# AVC-LAN-2.net
KiCad netlist of a schematic drawn in EAGLE
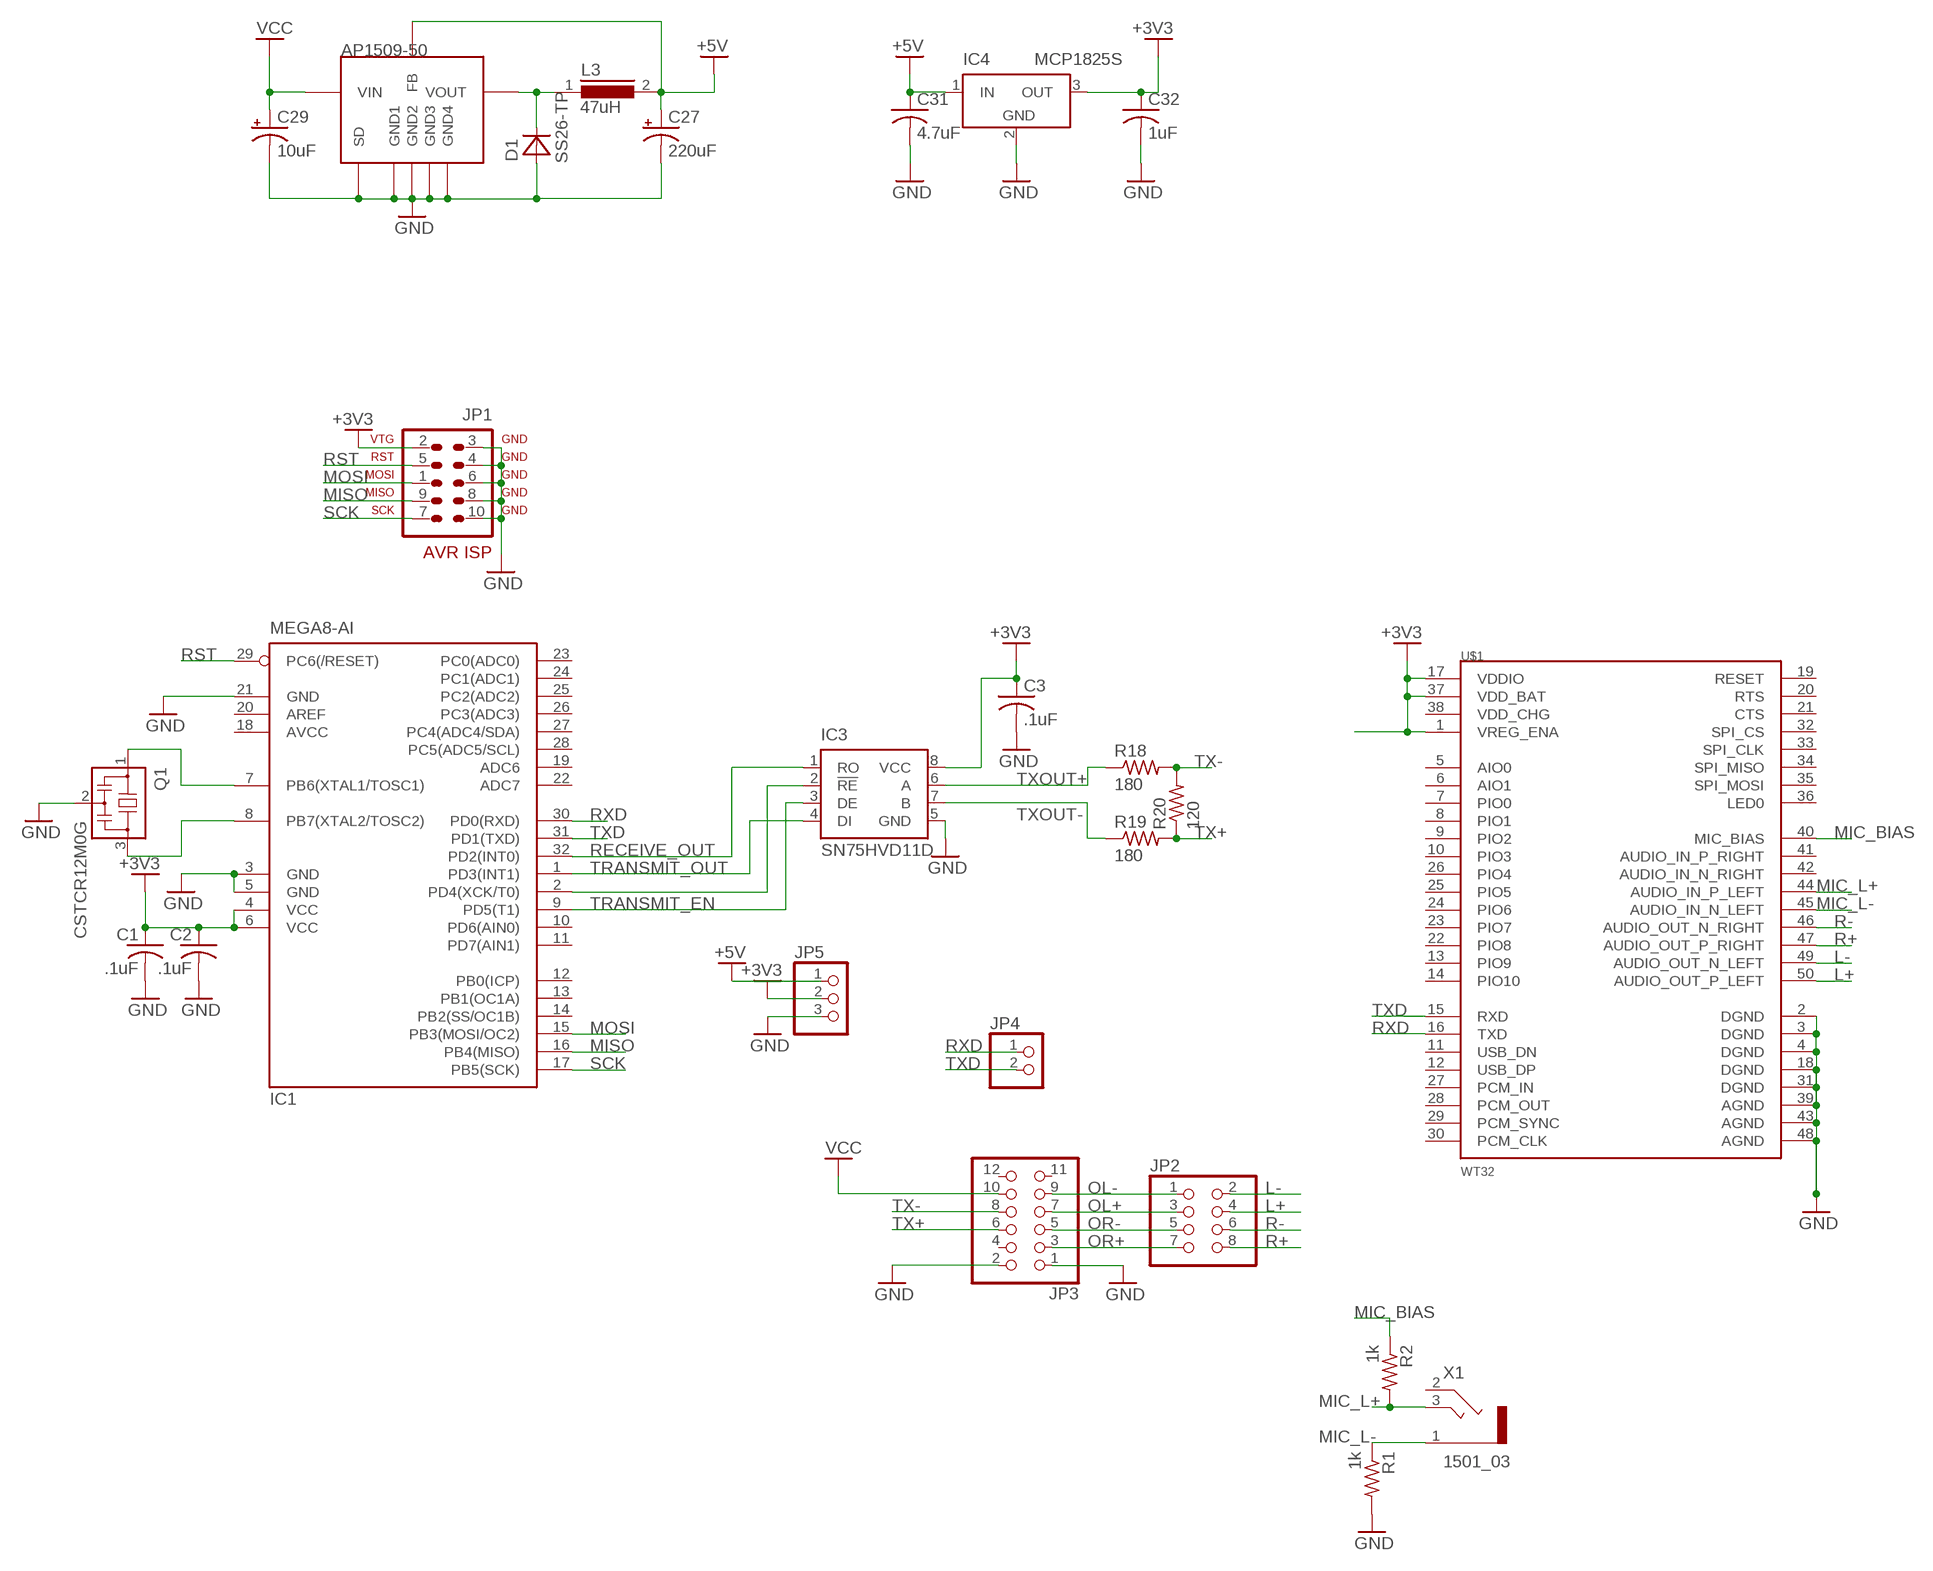
[diagram p0: schematic, sheet 1]

(export (version "E")
  (design (tool "Eeschema 10.0.6"))
  (components
    (comp (ref "C1")
      (value ".1uF")
      (footprint "eagle-import:C0603")
      (libsource (lib "eagle-import") (part "C-USC0603"))
    )
    (comp (ref "C2")
      (value ".1uF")
      (footprint "eagle-import:C0603")
      (libsource (lib "eagle-import") (part "C-USC0603"))
    )
    (comp (ref "C3")
      (value ".1uF")
      (footprint "eagle-import:C0603")
      (libsource (lib "eagle-import") (part "C-USC0603"))
    )
    (comp (ref "C27")
      (value "220uF")
      (footprint "eagle-import:D_7343-31W")
      (libsource (lib "eagle-import") (part "CPOL-USD/7343-31W"))
    )
    (comp (ref "C29")
      (value "10uF")
      (footprint "eagle-import:C_6032-28R")
      (libsource (lib "eagle-import") (part "CPOL-USC/6032-28R"))
    )
    (comp (ref "C31")
      (value "4.7uF")
      (footprint "eagle-import:C0603")
      (libsource (lib "eagle-import") (part "C-USC0603"))
    )
    (comp (ref "C32")
      (value "1uF")
      (footprint "eagle-import:C0603")
      (libsource (lib "eagle-import") (part "C-USC0603"))
    )
    (comp (ref "D1")
      (value "SS26-TP")
      (footprint "eagle-import:SMA")
      (libsource (lib "eagle-import") (part "MBRA340T3"))
    )
    (comp (ref "IC1")
      (value "MEGA8-AI")
      (footprint "eagle-import:TQFP32-08")
      (fields (field (name "MPN") "ATMEGA8-16AU"))
      (libsource (lib "eagle-import") (part "MEGA8-AI"))
    )
    (comp (ref "IC3")
      (value "SN75HVD11D")
      (footprint "eagle-import:SOIC8")
      (libsource (lib "eagle-import") (part "LTC485S"))
    )
    (comp (ref "IC4")
      (value "MCP1825S")
      (footprint "eagle-import:SOT223")
      (fields (field (name "MPN") "LT1963EST-3.3"))
      (libsource (lib "eagle-import") (part "LT1963EST-3.3"))
    )
    (comp (ref "JP1")
      (value "AVR-ISP-10R")
      (footprint "eagle-import:AVR-ISP-10R")
      (libsource (lib "eagle-import") (part "AVR-ISP-10R"))
    )
    (comp (ref "JP2")
      (value "PINHD-2X4")
      (footprint "eagle-import:2X04")
      (libsource (lib "eagle-import") (part "PINHD-2X4"))
    )
    (comp (ref "JP3")
      (value "PINHD-2X6/90")
      (footprint "eagle-import:2X06_90")
      (libsource (lib "eagle-import") (part "PINHD-2X6/90"))
    )
    (comp (ref "JP4")
      (value "PINHD-1X2")
      (footprint "eagle-import:1X02")
      (libsource (lib "eagle-import") (part "PINHD-1X2"))
    )
    (comp (ref "JP5")
      (value "PINHD-1X3")
      (footprint "eagle-import:1X03")
      (libsource (lib "eagle-import") (part "PINHD-1X3"))
    )
    (comp (ref "L3")
      (value "47uH")
      (footprint "eagle-import:DR125")
      (libsource (lib "eagle-import") (part "DR125"))
    )
    (comp (ref "Q1")
      (value "CSTCR12M0G")
      (footprint "eagle-import:CSTER12M")
      (fields (field (name "MPN") "CSTCC12M0") (field (name "MPN_1") "CSTCC12M0"))
      (libsource (lib "eagle-import") (part "CSTCR6M00G53Z"))
    )
    (comp (ref "R1")
      (value "1k")
      (footprint "eagle-import:R0603")
      (libsource (lib "eagle-import") (part "R-US_R0603"))
    )
    (comp (ref "R2")
      (value "1k")
      (footprint "eagle-import:R0603")
      (libsource (lib "eagle-import") (part "R-US_R0603"))
    )
    (comp (ref "R18")
      (value "180")
      (footprint "eagle-import:R0603")
      (libsource (lib "eagle-import") (part "R-US_R0603"))
    )
    (comp (ref "R19")
      (value "180")
      (footprint "eagle-import:R0603")
      (libsource (lib "eagle-import") (part "R-US_R0603"))
    )
    (comp (ref "R20")
      (value "120")
      (footprint "eagle-import:R0603")
      (libsource (lib "eagle-import") (part "R-US_R0603"))
    )
    (comp (ref "U$1")
      (value "WT32")
      (footprint "eagle-import:WT32")
      (libsource (lib "eagle-import") (part "WT32"))
    )
    (comp (ref "U$5")
      (value "AP1509-50")
      (footprint "eagle-import:SOP-8L")
      (libsource (lib "eagle-import") (part "AP1509-50"))
    )
    (comp (ref "X1")
      (value "1501_03")
      (footprint "eagle-import:1501_03")
      (libsource (lib "eagle-import") (part "1501_03"))
    )
  )
  (nets
    (net (code "1") (name "+3V3") (class "Default")
      (node (ref "C1") (pin "1") (pinfunction "1_1") (pintype "passive"))
      (node (ref "C2") (pin "1") (pinfunction "1_1") (pintype "passive"))
      (node (ref "C3") (pin "1") (pinfunction "1_1") (pintype "passive"))
      (node (ref "C32") (pin "1") (pinfunction "1_1") (pintype "passive"))
      (node (ref "IC1") (pin "4") (pinfunction "VCC_4") (pintype "power_in"))
      (node (ref "IC1") (pin "6") (pinfunction "VCC_6") (pintype "power_in"))
      (node (ref "IC3") (pin "8") (pinfunction "VCC_8") (pintype "input"))
      (node (ref "IC4") (pin "3") (pinfunction "OUT_3") (pintype "output"))
      (node (ref "JP1") (pin "2") (pinfunction "2_2") (pintype "passive"))
      (node (ref "JP5") (pin "2") (pinfunction "2_2") (pintype "passive"))
      (node (ref "U$1") (pin "1") (pinfunction "VREG_ENA_1") (pintype "bidirectional"))
      (node (ref "U$1") (pin "17") (pinfunction "VDDIO_17") (pintype "bidirectional"))
      (node (ref "U$1") (pin "37") (pinfunction "VDD_BAT_37") (pintype "bidirectional"))
    )
    (net (code "2") (name "+5V") (class "Default")
      (node (ref "C27") (pin "+") (pinfunction "+_+") (pintype "passive"))
      (node (ref "C31") (pin "1") (pinfunction "1_1") (pintype "passive"))
      (node (ref "IC4") (pin "1") (pinfunction "IN_1") (pintype "input"))
      (node (ref "JP5") (pin "1") (pinfunction "1_1") (pintype "passive"))
      (node (ref "L3") (pin "2") (pinfunction "2_2") (pintype "passive"))
      (node (ref "U$5") (pin "P$3") (pinfunction "FB_P$3") (pintype "bidirectional"))
    )
    (net (code "3") (name "/AVCC") (class "Default")
      (node (ref "IC1") (pin "18") (pinfunction "AVCC_18") (pintype "power_in"))
    )
    (net (code "4") (name "/L+") (class "Default")
      (node (ref "JP2") (pin "4") (pinfunction "4_4") (pintype "passive"))
      (node (ref "U$1") (pin "50") (pinfunction "AUDIO_OUT_P_LEFT_50") (pintype "bidirectional"))
    )
    (net (code "5") (name "/L-") (class "Default")
      (node (ref "JP2") (pin "2") (pinfunction "2_2") (pintype "passive"))
      (node (ref "U$1") (pin "49") (pinfunction "AUDIO_OUT_N_LEFT_49") (pintype "bidirectional"))
    )
    (net (code "6") (name "/MIC_BIAS") (class "Default")
      (node (ref "R2") (pin "1") (pinfunction "1_1") (pintype "passive"))
      (node (ref "U$1") (pin "40") (pinfunction "MIC_BIAS_40") (pintype "bidirectional"))
    )
    (net (code "7") (name "/MIC_L+") (class "Default")
      (node (ref "R2") (pin "2") (pinfunction "2_2") (pintype "passive"))
      (node (ref "U$1") (pin "44") (pinfunction "AUDIO_IN_P_LEFT_44") (pintype "bidirectional"))
      (node (ref "X1") (pin "3") (pinfunction "3_3") (pintype "passive"))
    )
    (net (code "8") (name "/MIC_L-") (class "Default")
      (node (ref "R1") (pin "1") (pinfunction "1_1") (pintype "passive"))
      (node (ref "U$1") (pin "45") (pinfunction "AUDIO_IN_N_LEFT_45") (pintype "bidirectional"))
      (node (ref "X1") (pin "1") (pinfunction "1_1") (pintype "passive"))
    )
    (net (code "9") (name "/MISO") (class "Default")
      (node (ref "IC1") (pin "16") (pinfunction "PB4(MISO)_16") (pintype "bidirectional"))
      (node (ref "JP1") (pin "9") (pinfunction "9_9") (pintype "passive"))
    )
    (net (code "10") (name "/MOSI") (class "Default")
      (node (ref "IC1") (pin "15") (pinfunction "PB3(MOSI/OC2)_15") (pintype "bidirectional"))
      (node (ref "JP1") (pin "1") (pinfunction "1_1") (pintype "passive"))
    )
    (net (code "11") (name "/OL+") (class "Default")
      (node (ref "JP2") (pin "3") (pinfunction "3_3") (pintype "passive"))
      (node (ref "JP3") (pin "7") (pinfunction "7_7") (pintype "passive"))
    )
    (net (code "12") (name "/OL-") (class "Default")
      (node (ref "JP2") (pin "1") (pinfunction "1_1") (pintype "passive"))
      (node (ref "JP3") (pin "9") (pinfunction "9_9") (pintype "passive"))
    )
    (net (code "13") (name "/OR+") (class "Default")
      (node (ref "JP2") (pin "7") (pinfunction "7_7") (pintype "passive"))
      (node (ref "JP3") (pin "3") (pinfunction "3_3") (pintype "passive"))
    )
    (net (code "14") (name "/OR-") (class "Default")
      (node (ref "JP2") (pin "5") (pinfunction "5_5") (pintype "passive"))
      (node (ref "JP3") (pin "5") (pinfunction "5_5") (pintype "passive"))
    )
    (net (code "15") (name "/R+") (class "Default")
      (node (ref "JP2") (pin "8") (pinfunction "8_8") (pintype "passive"))
      (node (ref "U$1") (pin "47") (pinfunction "AUDIO_OUT_P_RIGHT_47") (pintype "bidirectional"))
    )
    (net (code "16") (name "/R-") (class "Default")
      (node (ref "JP2") (pin "6") (pinfunction "6_6") (pintype "passive"))
      (node (ref "U$1") (pin "46") (pinfunction "AUDIO_OUT_N_RIGHT_46") (pintype "bidirectional"))
    )
    (net (code "17") (name "/RECEIVE_OUT") (class "Default")
      (node (ref "IC1") (pin "32") (pinfunction "PD2(INT0)_32") (pintype "bidirectional"))
      (node (ref "IC3") (pin "1") (pinfunction "RO_1") (pintype "output"))
    )
    (net (code "18") (name "/RST") (class "Default")
      (node (ref "IC1") (pin "29") (pinfunction "PC6(/RESET)_29") (pintype "bidirectional"))
      (node (ref "JP1") (pin "5") (pinfunction "5_5") (pintype "passive"))
    )
    (net (code "19") (name "/RXD") (class "Default")
      (node (ref "IC1") (pin "30") (pinfunction "PD0(RXD)_30") (pintype "bidirectional"))
      (node (ref "JP4") (pin "1") (pinfunction "1_1") (pintype "passive"))
      (node (ref "U$1") (pin "16") (pinfunction "TXD_16") (pintype "bidirectional"))
    )
    (net (code "20") (name "/SCK") (class "Default")
      (node (ref "IC1") (pin "17") (pinfunction "PB5(SCK)_17") (pintype "bidirectional"))
      (node (ref "JP1") (pin "7") (pinfunction "7_7") (pintype "passive"))
    )
    (net (code "21") (name "/TRANSMIT_EN") (class "Default")
      (node (ref "IC1") (pin "9") (pinfunction "PD5(T1)_9") (pintype "bidirectional"))
      (node (ref "IC3") (pin "3") (pinfunction "DE_3") (pintype "input"))
    )
    (net (code "22") (name "/TRANSMIT_OUT") (class "Default")
      (node (ref "IC1") (pin "1") (pinfunction "PD3(INT1)_1") (pintype "bidirectional"))
      (node (ref "IC3") (pin "4") (pinfunction "DI_4") (pintype "input"))
    )
    (net (code "23") (name "/TX+") (class "Default")
      (node (ref "JP3") (pin "6") (pinfunction "6_6") (pintype "passive"))
      (node (ref "R19") (pin "2") (pinfunction "2_2") (pintype "passive"))
      (node (ref "R20") (pin "1") (pinfunction "1_1") (pintype "passive"))
    )
    (net (code "24") (name "/TX-") (class "Default")
      (node (ref "JP3") (pin "8") (pinfunction "8_8") (pintype "passive"))
      (node (ref "R18") (pin "2") (pinfunction "2_2") (pintype "passive"))
      (node (ref "R20") (pin "2") (pinfunction "2_2") (pintype "passive"))
    )
    (net (code "25") (name "/TXD") (class "Default")
      (node (ref "IC1") (pin "31") (pinfunction "PD1(TXD)_31") (pintype "bidirectional"))
      (node (ref "JP4") (pin "2") (pinfunction "2_2") (pintype "passive"))
      (node (ref "U$1") (pin "15") (pinfunction "RXD_15") (pintype "bidirectional"))
    )
    (net (code "26") (name "/TXOUT+") (class "Default")
      (node (ref "IC3") (pin "6") (pinfunction "A_6") (pintype "bidirectional"))
      (node (ref "R18") (pin "1") (pinfunction "1_1") (pintype "passive"))
    )
    (net (code "27") (name "/TXOUT-") (class "Default")
      (node (ref "IC3") (pin "7") (pinfunction "B_7") (pintype "bidirectional"))
      (node (ref "R19") (pin "1") (pinfunction "1_1") (pintype "passive"))
    )
    (net (code "28") (name "GND") (class "Default")
      (node (ref "C1") (pin "2") (pinfunction "2_2") (pintype "passive"))
      (node (ref "C2") (pin "2") (pinfunction "2_2") (pintype "passive"))
      (node (ref "C27") (pin "-") (pinfunction "-_-") (pintype "passive"))
      (node (ref "C29") (pin "-") (pinfunction "-_-") (pintype "passive"))
      (node (ref "C3") (pin "2") (pinfunction "2_2") (pintype "passive"))
      (node (ref "C31") (pin "2") (pinfunction "2_2") (pintype "passive"))
      (node (ref "C32") (pin "2") (pinfunction "2_2") (pintype "passive"))
      (node (ref "D1") (pin "A") (pinfunction "A_A") (pintype "passive"))
      (node (ref "IC1") (pin "21") (pinfunction "GND_21") (pintype "power_in"))
      (node (ref "IC1") (pin "3") (pinfunction "GND_3") (pintype "power_in"))
      (node (ref "IC1") (pin "5") (pinfunction "GND_5") (pintype "power_in"))
      (node (ref "IC3") (pin "5") (pinfunction "GND_5") (pintype "input"))
      (node (ref "IC4") (pin "2") (pinfunction "GND_2") (pintype "power_in"))
      (node (ref "JP1") (pin "10") (pinfunction "10_10") (pintype "passive"))
      (node (ref "JP1") (pin "3") (pinfunction "3_3") (pintype "passive"))
      (node (ref "JP1") (pin "4") (pinfunction "4_4") (pintype "passive"))
      (node (ref "JP1") (pin "6") (pinfunction "6_6") (pintype "passive"))
      (node (ref "JP1") (pin "8") (pinfunction "8_8") (pintype "passive"))
      (node (ref "JP3") (pin "1") (pinfunction "1_1") (pintype "passive"))
      (node (ref "JP3") (pin "2") (pinfunction "2_2") (pintype "passive"))
      (node (ref "JP5") (pin "3") (pinfunction "3_3") (pintype "passive"))
      (node (ref "Q1") (pin "2") (pinfunction "2_2") (pintype "passive"))
      (node (ref "R1") (pin "2") (pinfunction "2_2") (pintype "passive"))
      (node (ref "U$1") (pin "18") (pinfunction "DGND_18") (pintype "bidirectional"))
      (node (ref "U$1") (pin "2") (pinfunction "DGND_2") (pintype "bidirectional"))
      (node (ref "U$1") (pin "3") (pinfunction "DGND_3") (pintype "bidirectional"))
      (node (ref "U$1") (pin "31") (pinfunction "DGND_31") (pintype "bidirectional"))
      (node (ref "U$1") (pin "39") (pinfunction "AGND_39") (pintype "bidirectional"))
      (node (ref "U$1") (pin "4") (pinfunction "DGND_4") (pintype "bidirectional"))
      (node (ref "U$1") (pin "43") (pinfunction "AGND_43") (pintype "bidirectional"))
      (node (ref "U$1") (pin "48") (pinfunction "AGND_48") (pintype "bidirectional"))
      (node (ref "U$5") (pin "P$4") (pinfunction "SD_P$4") (pintype "bidirectional"))
      (node (ref "U$5") (pin "P$5") (pinfunction "GND1_P$5") (pintype "bidirectional"))
      (node (ref "U$5") (pin "P$6") (pinfunction "GND2_P$6") (pintype "bidirectional"))
      (node (ref "U$5") (pin "P$7") (pinfunction "GND3_P$7") (pintype "bidirectional"))
      (node (ref "U$5") (pin "P$8") (pinfunction "GND4_P$8") (pintype "bidirectional"))
    )
    (net (code "29") (name "Net-(IC1-PB6(XTAL1{slash}TOSC1))") (class "Default")
      (node (ref "IC1") (pin "7") (pinfunction "PB6(XTAL1/TOSC1)_7") (pintype "bidirectional"))
      (node (ref "Q1") (pin "1") (pinfunction "1_1") (pintype "passive"))
    )
    (net (code "30") (name "Net-(IC1-PB7(XTAL2{slash}TOSC2))") (class "Default")
      (node (ref "IC1") (pin "8") (pinfunction "PB7(XTAL2/TOSC2)_8") (pintype "bidirectional"))
      (node (ref "Q1") (pin "3") (pinfunction "3_3") (pintype "passive"))
    )
    (net (code "31") (name "Net-(IC1-PD4(XCK{slash}T0))") (class "Default")
      (node (ref "IC1") (pin "2") (pinfunction "PD4(XCK/T0)_2") (pintype "bidirectional"))
      (node (ref "IC3") (pin "2") (pinfunction "~{RE}_2") (pintype "input"))
    )
    (net (code "32") (name "Net-(U$5-VOUT)") (class "Default")
      (node (ref "D1") (pin "C") (pinfunction "C_C") (pintype "passive"))
      (node (ref "L3") (pin "1") (pinfunction "1_1") (pintype "passive"))
      (node (ref "U$5") (pin "P$2") (pinfunction "VOUT_P$2") (pintype "power_in"))
    )
    (net (code "33") (name "VCC") (class "Default")
      (node (ref "C29") (pin "+") (pinfunction "+_+") (pintype "passive"))
      (node (ref "JP3") (pin "10") (pinfunction "10_10") (pintype "passive"))
      (node (ref "U$5") (pin "P$1") (pinfunction "VIN_P$1") (pintype "power_in"))
    )
    (net (code "34") (name "unconnected-(IC1-ADC6-Pad19)") (class "Default")
      (node (ref "IC1") (pin "19") (pinfunction "ADC6_19") (pintype "bidirectional"))
    )
    (net (code "35") (name "unconnected-(IC1-ADC7-Pad22)") (class "Default")
      (node (ref "IC1") (pin "22") (pinfunction "ADC7_22") (pintype "bidirectional"))
    )
    (net (code "36") (name "unconnected-(IC1-AREF-Pad20)") (class "Default")
      (node (ref "IC1") (pin "20") (pinfunction "AREF_20") (pintype "passive"))
    )
    (net (code "37") (name "unconnected-(IC1-PB0(ICP)-Pad12)") (class "Default")
      (node (ref "IC1") (pin "12") (pinfunction "PB0(ICP)_12") (pintype "bidirectional"))
    )
    (net (code "38") (name "unconnected-(IC1-PB1(OC1A)-Pad13)") (class "Default")
      (node (ref "IC1") (pin "13") (pinfunction "PB1(OC1A)_13") (pintype "bidirectional"))
    )
    (net (code "39") (name "unconnected-(IC1-PB2(SS{slash}OC1B)-Pad14)") (class "Default")
      (node (ref "IC1") (pin "14") (pinfunction "PB2(SS/OC1B)_14") (pintype "bidirectional"))
    )
    (net (code "40") (name "unconnected-(IC1-PC0(ADC0)-Pad23)") (class "Default")
      (node (ref "IC1") (pin "23") (pinfunction "PC0(ADC0)_23") (pintype "bidirectional"))
    )
    (net (code "41") (name "unconnected-(IC1-PC1(ADC1)-Pad24)") (class "Default")
      (node (ref "IC1") (pin "24") (pinfunction "PC1(ADC1)_24") (pintype "bidirectional"))
    )
    (net (code "42") (name "unconnected-(IC1-PC2(ADC2)-Pad25)") (class "Default")
      (node (ref "IC1") (pin "25") (pinfunction "PC2(ADC2)_25") (pintype "bidirectional"))
    )
    (net (code "43") (name "unconnected-(IC1-PC3(ADC3)-Pad26)") (class "Default")
      (node (ref "IC1") (pin "26") (pinfunction "PC3(ADC3)_26") (pintype "bidirectional"))
    )
    (net (code "44") (name "unconnected-(IC1-PC4(ADC4{slash}SDA)-Pad27)") (class "Default")
      (node (ref "IC1") (pin "27") (pinfunction "PC4(ADC4/SDA)_27") (pintype "bidirectional"))
    )
    (net (code "45") (name "unconnected-(IC1-PC5(ADC5{slash}SCL)-Pad28)") (class "Default")
      (node (ref "IC1") (pin "28") (pinfunction "PC5(ADC5/SCL)_28") (pintype "bidirectional"))
    )
    (net (code "46") (name "unconnected-(IC1-PD6(AIN0)-Pad10)") (class "Default")
      (node (ref "IC1") (pin "10") (pinfunction "PD6(AIN0)_10") (pintype "bidirectional"))
    )
    (net (code "47") (name "unconnected-(IC1-PD7(AIN1)-Pad11)") (class "Default")
      (node (ref "IC1") (pin "11") (pinfunction "PD7(AIN1)_11") (pintype "bidirectional"))
    )
    (net (code "48") (name "unconnected-(JP3-Pad4)") (class "Default")
      (node (ref "JP3") (pin "4") (pinfunction "4_4") (pintype "passive"))
    )
    (net (code "49") (name "unconnected-(JP3-Pad11)") (class "Default")
      (node (ref "JP3") (pin "11") (pinfunction "11_11") (pintype "passive"))
    )
    (net (code "50") (name "unconnected-(JP3-Pad12)") (class "Default")
      (node (ref "JP3") (pin "12") (pinfunction "12_12") (pintype "passive"))
    )
    (net (code "51") (name "unconnected-(U$1-AIO0-Pad5)") (class "Default")
      (node (ref "U$1") (pin "5") (pinfunction "AIO0_5") (pintype "bidirectional"))
    )
    (net (code "52") (name "unconnected-(U$1-AIO1-Pad6)") (class "Default")
      (node (ref "U$1") (pin "6") (pinfunction "AIO1_6") (pintype "bidirectional"))
    )
    (net (code "53") (name "unconnected-(U$1-AUDIO_IN_N_RIGHT-Pad42)") (class "Default")
      (node (ref "U$1") (pin "42") (pinfunction "AUDIO_IN_N_RIGHT_42") (pintype "bidirectional"))
    )
    (net (code "54") (name "unconnected-(U$1-AUDIO_IN_P_RIGHT-Pad41)") (class "Default")
      (node (ref "U$1") (pin "41") (pinfunction "AUDIO_IN_P_RIGHT_41") (pintype "bidirectional"))
    )
    (net (code "55") (name "unconnected-(U$1-CTS-Pad21)") (class "Default")
      (node (ref "U$1") (pin "21") (pinfunction "CTS_21") (pintype "bidirectional"))
    )
    (net (code "56") (name "unconnected-(U$1-LED0-Pad36)") (class "Default")
      (node (ref "U$1") (pin "36") (pinfunction "LED0_36") (pintype "bidirectional"))
    )
    (net (code "57") (name "unconnected-(U$1-PCM_CLK-Pad30)") (class "Default")
      (node (ref "U$1") (pin "30") (pinfunction "PCM_CLK_30") (pintype "bidirectional"))
    )
    (net (code "58") (name "unconnected-(U$1-PCM_IN-Pad27)") (class "Default")
      (node (ref "U$1") (pin "27") (pinfunction "PCM_IN_27") (pintype "bidirectional"))
    )
    (net (code "59") (name "unconnected-(U$1-PCM_OUT-Pad28)") (class "Default")
      (node (ref "U$1") (pin "28") (pinfunction "PCM_OUT_28") (pintype "bidirectional"))
    )
    (net (code "60") (name "unconnected-(U$1-PCM_SYNC-Pad29)") (class "Default")
      (node (ref "U$1") (pin "29") (pinfunction "PCM_SYNC_29") (pintype "bidirectional"))
    )
    (net (code "61") (name "unconnected-(U$1-PIO0-Pad7)") (class "Default")
      (node (ref "U$1") (pin "7") (pinfunction "PIO0_7") (pintype "bidirectional"))
    )
    (net (code "62") (name "unconnected-(U$1-PIO1-Pad8)") (class "Default")
      (node (ref "U$1") (pin "8") (pinfunction "PIO1_8") (pintype "bidirectional"))
    )
    (net (code "63") (name "unconnected-(U$1-PIO2-Pad9)") (class "Default")
      (node (ref "U$1") (pin "9") (pinfunction "PIO2_9") (pintype "bidirectional"))
    )
    (net (code "64") (name "unconnected-(U$1-PIO3-Pad10)") (class "Default")
      (node (ref "U$1") (pin "10") (pinfunction "PIO3_10") (pintype "bidirectional"))
    )
    (net (code "65") (name "unconnected-(U$1-PIO4-Pad26)") (class "Default")
      (node (ref "U$1") (pin "26") (pinfunction "PIO4_26") (pintype "bidirectional"))
    )
    (net (code "66") (name "unconnected-(U$1-PIO5-Pad25)") (class "Default")
      (node (ref "U$1") (pin "25") (pinfunction "PIO5_25") (pintype "bidirectional"))
    )
    (net (code "67") (name "unconnected-(U$1-PIO6-Pad24)") (class "Default")
      (node (ref "U$1") (pin "24") (pinfunction "PIO6_24") (pintype "bidirectional"))
    )
    (net (code "68") (name "unconnected-(U$1-PIO7-Pad23)") (class "Default")
      (node (ref "U$1") (pin "23") (pinfunction "PIO7_23") (pintype "bidirectional"))
    )
    (net (code "69") (name "unconnected-(U$1-PIO8-Pad22)") (class "Default")
      (node (ref "U$1") (pin "22") (pinfunction "PIO8_22") (pintype "bidirectional"))
    )
    (net (code "70") (name "unconnected-(U$1-PIO9-Pad13)") (class "Default")
      (node (ref "U$1") (pin "13") (pinfunction "PIO9_13") (pintype "bidirectional"))
    )
    (net (code "71") (name "unconnected-(U$1-PIO10-Pad14)") (class "Default")
      (node (ref "U$1") (pin "14") (pinfunction "PIO10_14") (pintype "bidirectional"))
    )
    (net (code "72") (name "unconnected-(U$1-RESET-Pad19)") (class "Default")
      (node (ref "U$1") (pin "19") (pinfunction "RESET_19") (pintype "bidirectional"))
    )
    (net (code "73") (name "unconnected-(U$1-RTS-Pad20)") (class "Default")
      (node (ref "U$1") (pin "20") (pinfunction "RTS_20") (pintype "bidirectional"))
    )
    (net (code "74") (name "unconnected-(U$1-SPI_CLK-Pad33)") (class "Default")
      (node (ref "U$1") (pin "33") (pinfunction "SPI_CLK_33") (pintype "bidirectional"))
    )
    (net (code "75") (name "unconnected-(U$1-SPI_CS-Pad32)") (class "Default")
      (node (ref "U$1") (pin "32") (pinfunction "SPI_CS_32") (pintype "bidirectional"))
    )
    (net (code "76") (name "unconnected-(U$1-SPI_MISO-Pad34)") (class "Default")
      (node (ref "U$1") (pin "34") (pinfunction "SPI_MISO_34") (pintype "bidirectional"))
    )
    (net (code "77") (name "unconnected-(U$1-SPI_MOSI-Pad35)") (class "Default")
      (node (ref "U$1") (pin "35") (pinfunction "SPI_MOSI_35") (pintype "bidirectional"))
    )
    (net (code "78") (name "unconnected-(U$1-USB_DN-Pad11)") (class "Default")
      (node (ref "U$1") (pin "11") (pinfunction "USB_DN_11") (pintype "bidirectional"))
    )
    (net (code "79") (name "unconnected-(U$1-USB_DP-Pad12)") (class "Default")
      (node (ref "U$1") (pin "12") (pinfunction "USB_DP_12") (pintype "bidirectional"))
    )
    (net (code "80") (name "unconnected-(U$1-VDD_CHG-Pad38)") (class "Default")
      (node (ref "U$1") (pin "38") (pinfunction "VDD_CHG_38") (pintype "bidirectional"))
    )
    (net (code "81") (name "unconnected-(X1-Pad2)") (class "Default")
      (node (ref "X1") (pin "2") (pinfunction "2_2") (pintype "passive"))
    )
  )
)
